# control_alpha0001.net
KiCad netlist of a schematic drawn in EAGLE
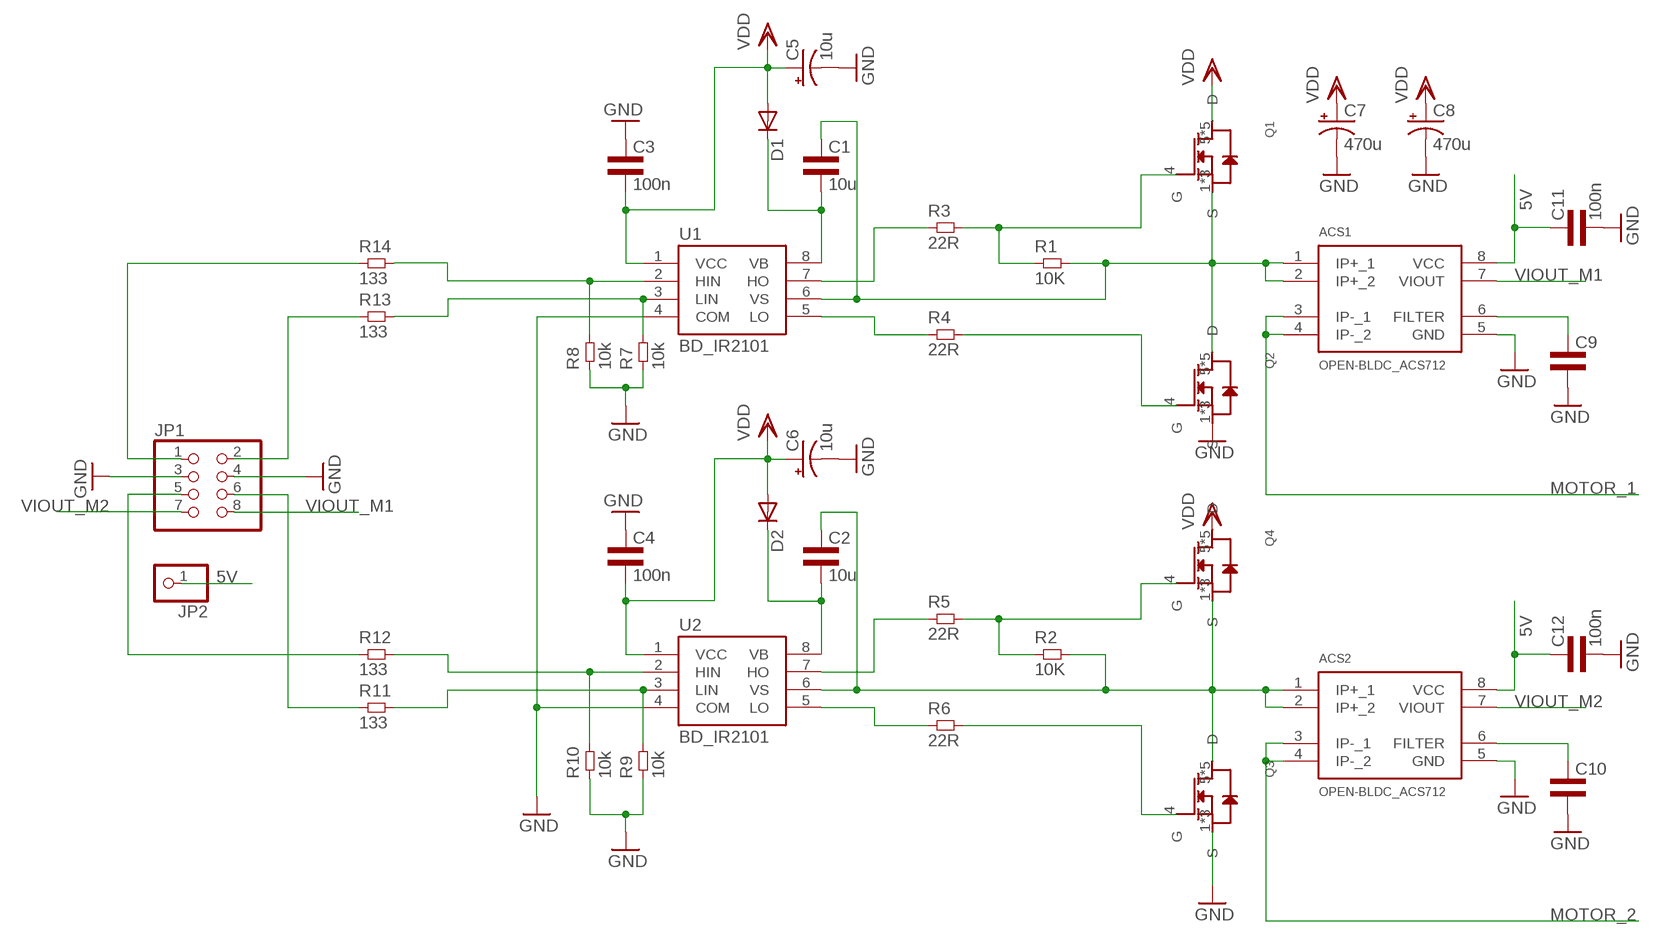
[diagram p0: schematic, sheet 1]

(export (version "E")
  (design (tool "Eeschema 10.0.6"))
  (components
    (comp (ref "ACS1")
      (value "OPEN-BLDC_ACS712")
      (footprint "eagle-import:OPEN-BLDC_SO8")
      (libsource (lib "eagle-import") (part "OPEN-BLDC_ACS712"))
    )
    (comp (ref "ACS2")
      (value "OPEN-BLDC_ACS712")
      (footprint "eagle-import:OPEN-BLDC_SO8")
      (libsource (lib "eagle-import") (part "OPEN-BLDC_ACS712"))
    )
    (comp (ref "C1")
      (value "10u")
      (footprint "eagle-import:0805L3")
      (libsource (lib "eagle-import") (part "CAP0805L3"))
    )
    (comp (ref "C2")
      (value "10u")
      (footprint "eagle-import:0805L3")
      (libsource (lib "eagle-import") (part "CAP0805L3"))
    )
    (comp (ref "C3")
      (value "100n")
      (footprint "eagle-import:0603L3")
      (libsource (lib "eagle-import") (part "CAP0603L3"))
    )
    (comp (ref "C4")
      (value "100n")
      (footprint "eagle-import:0603L3")
      (libsource (lib "eagle-import") (part "CAP0603L3"))
    )
    (comp (ref "C5")
      (value "10u")
      (footprint "eagle-import:E1,8-4")
      (libsource (lib "eagle-import") (part "CPOL-USE1.8-4"))
    )
    (comp (ref "C6")
      (value "10u")
      (footprint "eagle-import:E1,8-4")
      (libsource (lib "eagle-import") (part "CPOL-USE1.8-4"))
    )
    (comp (ref "C7")
      (value "470u")
      (footprint "eagle-import:E5-8,5")
      (libsource (lib "eagle-import") (part "CPOL-USE5-8.5"))
    )
    (comp (ref "C8")
      (value "470u")
      (footprint "eagle-import:E5-8,5")
      (libsource (lib "eagle-import") (part "CPOL-USE5-8.5"))
    )
    (comp (ref "C9")
      (value "CAP0603L3")
      (footprint "eagle-import:0603L3")
      (libsource (lib "eagle-import") (part "CAP0603L3"))
    )
    (comp (ref "C10")
      (value "CAP0603L3")
      (footprint "eagle-import:0603L3")
      (libsource (lib "eagle-import") (part "CAP0603L3"))
    )
    (comp (ref "C11")
      (value "100n")
      (footprint "eagle-import:0603L3")
      (libsource (lib "eagle-import") (part "CAP0603L3"))
    )
    (comp (ref "C12")
      (value "100n")
      (footprint "eagle-import:0603L3")
      (libsource (lib "eagle-import") (part "CAP0603L3"))
    )
    (comp (ref "D1")
      (value "DIODE-SMB")
      (footprint "eagle-import:SMB")
      (libsource (lib "eagle-import") (part "DIODE-SMB"))
    )
    (comp (ref "D2")
      (value "DIODE-SMB")
      (footprint "eagle-import:SMB")
      (libsource (lib "eagle-import") (part "DIODE-SMB"))
    )
    (comp (ref "JP1")
      (value "PINHD-2X4")
      (footprint "eagle-import:2X04")
      (libsource (lib "eagle-import") (part "PINHD-2X4"))
    )
    (comp (ref "JP2")
      (value "PINHD-1X1")
      (footprint "eagle-import:1X01")
      (libsource (lib "eagle-import") (part "PINHD-1X1"))
    )
    (comp (ref "Q1")
      (value "CSD18540Q5B")
      (footprint "eagle-import:Q5B")
      (libsource (lib "eagle-import") (part "CSD18540Q5B"))
    )
    (comp (ref "Q2")
      (value "CSD18540Q5B")
      (footprint "eagle-import:Q5B")
      (libsource (lib "eagle-import") (part "CSD18540Q5B"))
    )
    (comp (ref "Q3")
      (value "CSD18540Q5B")
      (footprint "eagle-import:Q5B")
      (libsource (lib "eagle-import") (part "CSD18540Q5B"))
    )
    (comp (ref "Q4")
      (value "CSD18540Q5B")
      (footprint "eagle-import:Q5B")
      (libsource (lib "eagle-import") (part "CSD18540Q5B"))
    )
    (comp (ref "R1")
      (value "10K")
      (footprint "eagle-import:0805L3")
      (libsource (lib "eagle-import") (part "RES0805L3"))
    )
    (comp (ref "R2")
      (value "10K")
      (footprint "eagle-import:0805L3")
      (libsource (lib "eagle-import") (part "RES0805L3"))
    )
    (comp (ref "R3")
      (value "22R")
      (footprint "eagle-import:0805L3")
      (libsource (lib "eagle-import") (part "RES0805L3"))
    )
    (comp (ref "R4")
      (value "22R")
      (footprint "eagle-import:0805L3")
      (libsource (lib "eagle-import") (part "RES0805L3"))
    )
    (comp (ref "R5")
      (value "22R")
      (footprint "eagle-import:0805L3")
      (libsource (lib "eagle-import") (part "RES0805L3"))
    )
    (comp (ref "R6")
      (value "22R")
      (footprint "eagle-import:0805L3")
      (libsource (lib "eagle-import") (part "RES0805L3"))
    )
    (comp (ref "R7")
      (value "10k")
      (footprint "eagle-import:0603L3")
      (libsource (lib "eagle-import") (part "RES0603L3"))
    )
    (comp (ref "R8")
      (value "10k")
      (footprint "eagle-import:0603L3")
      (libsource (lib "eagle-import") (part "RES0603L3"))
    )
    (comp (ref "R9")
      (value "10k")
      (footprint "eagle-import:0603L3")
      (libsource (lib "eagle-import") (part "RES0603L3"))
    )
    (comp (ref "R10")
      (value "10k")
      (footprint "eagle-import:0603L3")
      (libsource (lib "eagle-import") (part "RES0603L3"))
    )
    (comp (ref "R11")
      (value "133")
      (footprint "eagle-import:0603L3")
      (libsource (lib "eagle-import") (part "RES0603L3"))
    )
    (comp (ref "R12")
      (value "133")
      (footprint "eagle-import:0603L3")
      (libsource (lib "eagle-import") (part "RES0603L3"))
    )
    (comp (ref "R13")
      (value "133")
      (footprint "eagle-import:0603L3")
      (libsource (lib "eagle-import") (part "RES0603L3"))
    )
    (comp (ref "R14")
      (value "133")
      (footprint "eagle-import:0603L3")
      (libsource (lib "eagle-import") (part "RES0603L3"))
    )
    (comp (ref "U1")
      (value "BD_IR2101")
      (footprint "eagle-import:SO8")
      (libsource (lib "eagle-import") (part "BD_IR2101"))
    )
    (comp (ref "U2")
      (value "BD_IR2101")
      (footprint "eagle-import:SO8")
      (libsource (lib "eagle-import") (part "BD_IR2101"))
    )
  )
  (nets
    (net (code "1") (name "/5V") (class "Default")
      (node (ref "ACS1") (pin "8") (pinfunction "VCC_8") (pintype "bidirectional"))
      (node (ref "ACS2") (pin "8") (pinfunction "VCC_8") (pintype "bidirectional"))
      (node (ref "C11") (pin "P$1") (pinfunction "1_P$1") (pintype "bidirectional"))
      (node (ref "C12") (pin "P$1") (pinfunction "1_P$1") (pintype "bidirectional"))
      (node (ref "JP2") (pin "1") (pinfunction "1_1") (pintype "passive"))
    )
    (net (code "2") (name "/MOTOR_1") (class "Default")
      (node (ref "ACS1") (pin "3") (pinfunction "IP-_1_3") (pintype "bidirectional"))
      (node (ref "ACS1") (pin "4") (pinfunction "IP-_2_4") (pintype "bidirectional"))
    )
    (net (code "3") (name "/MOTOR_2") (class "Default")
      (node (ref "ACS2") (pin "3") (pinfunction "IP-_1_3") (pintype "bidirectional"))
      (node (ref "ACS2") (pin "4") (pinfunction "IP-_2_4") (pintype "bidirectional"))
    )
    (net (code "4") (name "/VIOUT_M1") (class "Default")
      (node (ref "ACS1") (pin "7") (pinfunction "VIOUT_7") (pintype "bidirectional"))
      (node (ref "JP1") (pin "8") (pinfunction "8_8") (pintype "passive"))
    )
    (net (code "5") (name "/VIOUT_M2") (class "Default")
      (node (ref "ACS2") (pin "7") (pinfunction "VIOUT_7") (pintype "bidirectional"))
      (node (ref "JP1") (pin "7") (pinfunction "7_7") (pintype "passive"))
    )
    (net (code "6") (name "GND") (class "Default")
      (node (ref "ACS1") (pin "5") (pinfunction "GND_5") (pintype "bidirectional"))
      (node (ref "ACS2") (pin "5") (pinfunction "GND_5") (pintype "bidirectional"))
      (node (ref "C10") (pin "P$2") (pinfunction "2_P$2") (pintype "bidirectional"))
      (node (ref "C11") (pin "P$2") (pinfunction "2_P$2") (pintype "bidirectional"))
      (node (ref "C12") (pin "P$2") (pinfunction "2_P$2") (pintype "bidirectional"))
      (node (ref "C3") (pin "P$1") (pinfunction "1_P$1") (pintype "bidirectional"))
      (node (ref "C4") (pin "P$1") (pinfunction "1_P$1") (pintype "bidirectional"))
      (node (ref "C5") (pin "-") (pinfunction "-_-") (pintype "passive"))
      (node (ref "C6") (pin "-") (pinfunction "-_-") (pintype "passive"))
      (node (ref "C7") (pin "-") (pinfunction "-_-") (pintype "passive"))
      (node (ref "C8") (pin "-") (pinfunction "-_-") (pintype "passive"))
      (node (ref "C9") (pin "P$2") (pinfunction "2_P$2") (pintype "bidirectional"))
      (node (ref "JP1") (pin "3") (pinfunction "3_3") (pintype "passive"))
      (node (ref "JP1") (pin "4") (pinfunction "4_4") (pintype "passive"))
      (node (ref "Q2") (pin "1") (pinfunction "S_1") (pintype "bidirectional"))
      (node (ref "Q2") (pin "2") (pinfunction "S_2") (pintype "bidirectional"))
      (node (ref "Q2") (pin "3") (pinfunction "S_3") (pintype "bidirectional"))
      (node (ref "Q3") (pin "1") (pinfunction "S_1") (pintype "bidirectional"))
      (node (ref "Q3") (pin "2") (pinfunction "S_2") (pintype "bidirectional"))
      (node (ref "Q3") (pin "3") (pinfunction "S_3") (pintype "bidirectional"))
      (node (ref "R10") (pin "P$1") (pinfunction "1_P$1") (pintype "bidirectional"))
      (node (ref "R7") (pin "P$1") (pinfunction "1_P$1") (pintype "bidirectional"))
      (node (ref "R8") (pin "P$1") (pinfunction "1_P$1") (pintype "bidirectional"))
      (node (ref "R9") (pin "P$1") (pinfunction "1_P$1") (pintype "bidirectional"))
      (node (ref "U1") (pin "4") (pinfunction "COM_4") (pintype "bidirectional"))
      (node (ref "U2") (pin "4") (pinfunction "COM_4") (pintype "bidirectional"))
    )
    (net (code "7") (name "Net-(ACS1-FILTER)") (class "Default")
      (node (ref "ACS1") (pin "6") (pinfunction "FILTER_6") (pintype "bidirectional"))
      (node (ref "C9") (pin "P$1") (pinfunction "1_P$1") (pintype "bidirectional"))
    )
    (net (code "8") (name "Net-(ACS1-IP+_1)") (class "Default")
      (node (ref "ACS1") (pin "1") (pinfunction "IP+_1_1") (pintype "bidirectional"))
      (node (ref "ACS1") (pin "2") (pinfunction "IP+_2_2") (pintype "bidirectional"))
      (node (ref "C1") (pin "1") (pinfunction "1_1") (pintype "bidirectional"))
      (node (ref "Q1") (pin "1") (pinfunction "S_1") (pintype "bidirectional"))
      (node (ref "Q1") (pin "2") (pinfunction "S_2") (pintype "bidirectional"))
      (node (ref "Q1") (pin "3") (pinfunction "S_3") (pintype "bidirectional"))
      (node (ref "Q2") (pin "5") (pinfunction "D_5") (pintype "bidirectional"))
      (node (ref "Q2") (pin "6") (pinfunction "D_6") (pintype "bidirectional"))
      (node (ref "Q2") (pin "7") (pinfunction "D_7") (pintype "bidirectional"))
      (node (ref "Q2") (pin "8") (pinfunction "D_8") (pintype "bidirectional"))
      (node (ref "Q2") (pin "9") (pinfunction "D_9") (pintype "bidirectional"))
      (node (ref "R1") (pin "2") (pinfunction "2_2") (pintype "bidirectional"))
      (node (ref "U1") (pin "6") (pinfunction "VS_6") (pintype "bidirectional"))
    )
    (net (code "9") (name "Net-(ACS2-FILTER)") (class "Default")
      (node (ref "ACS2") (pin "6") (pinfunction "FILTER_6") (pintype "bidirectional"))
      (node (ref "C10") (pin "P$1") (pinfunction "1_P$1") (pintype "bidirectional"))
    )
    (net (code "10") (name "Net-(ACS2-IP+_1)") (class "Default")
      (node (ref "ACS2") (pin "1") (pinfunction "IP+_1_1") (pintype "bidirectional"))
      (node (ref "ACS2") (pin "2") (pinfunction "IP+_2_2") (pintype "bidirectional"))
      (node (ref "C2") (pin "1") (pinfunction "1_1") (pintype "bidirectional"))
      (node (ref "Q3") (pin "5") (pinfunction "D_5") (pintype "bidirectional"))
      (node (ref "Q3") (pin "6") (pinfunction "D_6") (pintype "bidirectional"))
      (node (ref "Q3") (pin "7") (pinfunction "D_7") (pintype "bidirectional"))
      (node (ref "Q3") (pin "8") (pinfunction "D_8") (pintype "bidirectional"))
      (node (ref "Q3") (pin "9") (pinfunction "D_9") (pintype "bidirectional"))
      (node (ref "Q4") (pin "1") (pinfunction "S_1") (pintype "bidirectional"))
      (node (ref "Q4") (pin "2") (pinfunction "S_2") (pintype "bidirectional"))
      (node (ref "Q4") (pin "3") (pinfunction "S_3") (pintype "bidirectional"))
      (node (ref "R2") (pin "2") (pinfunction "2_2") (pintype "bidirectional"))
      (node (ref "U2") (pin "6") (pinfunction "VS_6") (pintype "bidirectional"))
    )
    (net (code "11") (name "Net-(Q1-G)") (class "Default")
      (node (ref "Q1") (pin "4") (pinfunction "G_4") (pintype "bidirectional"))
      (node (ref "R1") (pin "1") (pinfunction "1_1") (pintype "bidirectional"))
      (node (ref "R3") (pin "2") (pinfunction "2_2") (pintype "bidirectional"))
    )
    (net (code "12") (name "Net-(Q2-G)") (class "Default")
      (node (ref "Q2") (pin "4") (pinfunction "G_4") (pintype "bidirectional"))
      (node (ref "R4") (pin "2") (pinfunction "2_2") (pintype "bidirectional"))
    )
    (net (code "13") (name "Net-(Q3-G)") (class "Default")
      (node (ref "Q3") (pin "4") (pinfunction "G_4") (pintype "bidirectional"))
      (node (ref "R6") (pin "2") (pinfunction "2_2") (pintype "bidirectional"))
    )
    (net (code "14") (name "Net-(Q4-G)") (class "Default")
      (node (ref "Q4") (pin "4") (pinfunction "G_4") (pintype "bidirectional"))
      (node (ref "R2") (pin "1") (pinfunction "1_1") (pintype "bidirectional"))
      (node (ref "R5") (pin "2") (pinfunction "2_2") (pintype "bidirectional"))
    )
    (net (code "15") (name "Net-(R10-2)") (class "Default")
      (node (ref "R10") (pin "P$2") (pinfunction "2_P$2") (pintype "bidirectional"))
      (node (ref "R12") (pin "P$2") (pinfunction "2_P$2") (pintype "bidirectional"))
      (node (ref "U2") (pin "2") (pinfunction "HIN_2") (pintype "bidirectional"))
    )
    (net (code "16") (name "Net-(R11-1)") (class "Default")
      (node (ref "JP1") (pin "6") (pinfunction "6_6") (pintype "passive"))
      (node (ref "R11") (pin "P$1") (pinfunction "1_P$1") (pintype "bidirectional"))
    )
    (net (code "17") (name "Net-(R11-2)") (class "Default")
      (node (ref "R11") (pin "P$2") (pinfunction "2_P$2") (pintype "bidirectional"))
      (node (ref "R9") (pin "P$2") (pinfunction "2_P$2") (pintype "bidirectional"))
      (node (ref "U2") (pin "3") (pinfunction "LIN_3") (pintype "bidirectional"))
    )
    (net (code "18") (name "Net-(R12-1)") (class "Default")
      (node (ref "JP1") (pin "5") (pinfunction "5_5") (pintype "passive"))
      (node (ref "R12") (pin "P$1") (pinfunction "1_P$1") (pintype "bidirectional"))
    )
    (net (code "19") (name "Net-(R13-1)") (class "Default")
      (node (ref "JP1") (pin "2") (pinfunction "2_2") (pintype "passive"))
      (node (ref "R13") (pin "P$1") (pinfunction "1_P$1") (pintype "bidirectional"))
    )
    (net (code "20") (name "Net-(R13-2)") (class "Default")
      (node (ref "R13") (pin "P$2") (pinfunction "2_P$2") (pintype "bidirectional"))
      (node (ref "R7") (pin "P$2") (pinfunction "2_P$2") (pintype "bidirectional"))
      (node (ref "U1") (pin "3") (pinfunction "LIN_3") (pintype "bidirectional"))
    )
    (net (code "21") (name "Net-(R14-1)") (class "Default")
      (node (ref "JP1") (pin "1") (pinfunction "1_1") (pintype "passive"))
      (node (ref "R14") (pin "P$1") (pinfunction "1_P$1") (pintype "bidirectional"))
    )
    (net (code "22") (name "Net-(R14-2)") (class "Default")
      (node (ref "R14") (pin "P$2") (pinfunction "2_P$2") (pintype "bidirectional"))
      (node (ref "R8") (pin "P$2") (pinfunction "2_P$2") (pintype "bidirectional"))
      (node (ref "U1") (pin "2") (pinfunction "HIN_2") (pintype "bidirectional"))
    )
    (net (code "23") (name "Net-(U1-HO)") (class "Default")
      (node (ref "R3") (pin "1") (pinfunction "1_1") (pintype "bidirectional"))
      (node (ref "U1") (pin "7") (pinfunction "HO_7") (pintype "bidirectional"))
    )
    (net (code "24") (name "Net-(U1-LO)") (class "Default")
      (node (ref "R4") (pin "1") (pinfunction "1_1") (pintype "bidirectional"))
      (node (ref "U1") (pin "5") (pinfunction "LO_5") (pintype "bidirectional"))
    )
    (net (code "25") (name "Net-(U1-VB)") (class "Default")
      (node (ref "C1") (pin "2") (pinfunction "2_2") (pintype "bidirectional"))
      (node (ref "D1") (pin "C") (pinfunction "C_C") (pintype "passive"))
      (node (ref "U1") (pin "8") (pinfunction "VB_8") (pintype "bidirectional"))
    )
    (net (code "26") (name "Net-(U2-HO)") (class "Default")
      (node (ref "R5") (pin "1") (pinfunction "1_1") (pintype "bidirectional"))
      (node (ref "U2") (pin "7") (pinfunction "HO_7") (pintype "bidirectional"))
    )
    (net (code "27") (name "Net-(U2-LO)") (class "Default")
      (node (ref "R6") (pin "1") (pinfunction "1_1") (pintype "bidirectional"))
      (node (ref "U2") (pin "5") (pinfunction "LO_5") (pintype "bidirectional"))
    )
    (net (code "28") (name "Net-(U2-VB)") (class "Default")
      (node (ref "C2") (pin "2") (pinfunction "2_2") (pintype "bidirectional"))
      (node (ref "D2") (pin "C") (pinfunction "C_C") (pintype "passive"))
      (node (ref "U2") (pin "8") (pinfunction "VB_8") (pintype "bidirectional"))
    )
    (net (code "29") (name "VDD") (class "Default")
      (node (ref "C3") (pin "P$2") (pinfunction "2_P$2") (pintype "bidirectional"))
      (node (ref "C4") (pin "P$2") (pinfunction "2_P$2") (pintype "bidirectional"))
      (node (ref "C5") (pin "+") (pinfunction "+_+") (pintype "passive"))
      (node (ref "C6") (pin "+") (pinfunction "+_+") (pintype "passive"))
      (node (ref "C7") (pin "+") (pinfunction "+_+") (pintype "passive"))
      (node (ref "C8") (pin "+") (pinfunction "+_+") (pintype "passive"))
      (node (ref "D1") (pin "A") (pinfunction "A_A") (pintype "passive"))
      (node (ref "D2") (pin "A") (pinfunction "A_A") (pintype "passive"))
      (node (ref "Q1") (pin "5") (pinfunction "D_5") (pintype "bidirectional"))
      (node (ref "Q1") (pin "6") (pinfunction "D_6") (pintype "bidirectional"))
      (node (ref "Q1") (pin "7") (pinfunction "D_7") (pintype "bidirectional"))
      (node (ref "Q1") (pin "8") (pinfunction "D_8") (pintype "bidirectional"))
      (node (ref "Q1") (pin "9") (pinfunction "D_9") (pintype "bidirectional"))
      (node (ref "Q4") (pin "5") (pinfunction "D_5") (pintype "bidirectional"))
      (node (ref "Q4") (pin "6") (pinfunction "D_6") (pintype "bidirectional"))
      (node (ref "Q4") (pin "7") (pinfunction "D_7") (pintype "bidirectional"))
      (node (ref "Q4") (pin "8") (pinfunction "D_8") (pintype "bidirectional"))
      (node (ref "Q4") (pin "9") (pinfunction "D_9") (pintype "bidirectional"))
      (node (ref "U1") (pin "1") (pinfunction "VCC_1") (pintype "bidirectional"))
      (node (ref "U2") (pin "1") (pinfunction "VCC_1") (pintype "bidirectional"))
    )
  )
)
